# FrontPanel.net
KiCad netlist of a schematic drawn in EAGLE
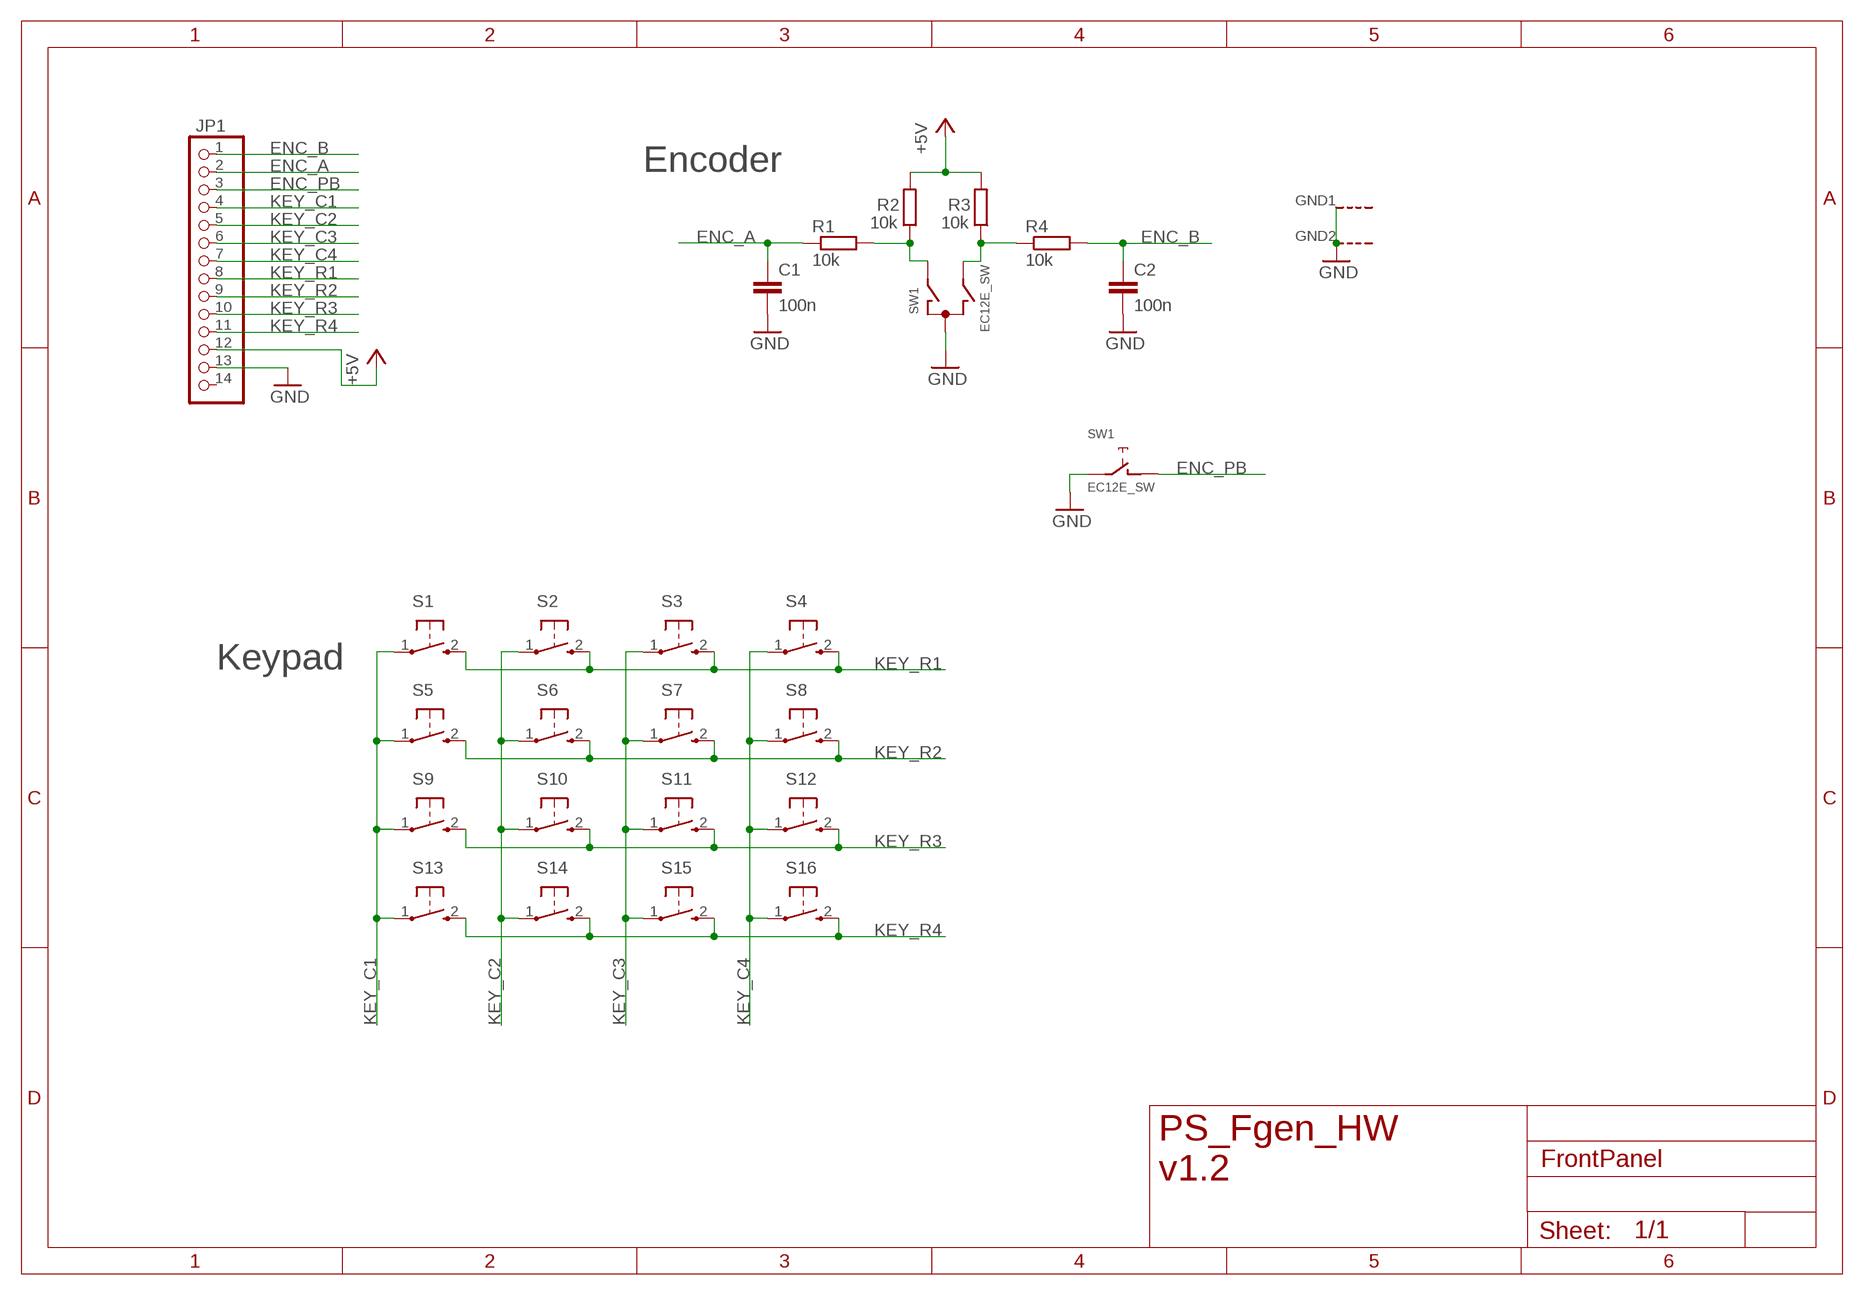
[diagram p0: schematic, sheet 1]

(export (version "E")
  (design (tool "Eeschema 10.0.6"))
  (components
    (comp (ref "C1")
      (value "100n")
      (footprint "eagle-import:C0805")
      (libsource (lib "eagle-import") (part "C-EUC0805"))
    )
    (comp (ref "C2")
      (value "100n")
      (footprint "eagle-import:C0805")
      (libsource (lib "eagle-import") (part "C-EUC0805"))
    )
    (comp (ref "JP1")
      (value "PINHD-1X14")
      (footprint "eagle-import:1X14")
      (libsource (lib "eagle-import") (part "PINHD-1X14"))
    )
    (comp (ref "R1")
      (value "10k")
      (footprint "eagle-import:R0805")
      (libsource (lib "eagle-import") (part "R-EU_R0805"))
    )
    (comp (ref "R2")
      (value "10k")
      (footprint "eagle-import:R0805")
      (libsource (lib "eagle-import") (part "R-EU_R0805"))
    )
    (comp (ref "R3")
      (value "10k")
      (footprint "eagle-import:R0805")
      (libsource (lib "eagle-import") (part "R-EU_R0805"))
    )
    (comp (ref "R4")
      (value "10k")
      (footprint "eagle-import:R0805")
      (libsource (lib "eagle-import") (part "R-EU_R0805"))
    )
    (comp (ref "S1")
      (value "KURZHUBTASTER")
      (footprint "eagle-import:B3F-10XX")
      (libsource (lib "eagle-import") (part "KURZHUBTASTER"))
    )
    (comp (ref "S2")
      (value "KURZHUBTASTER")
      (footprint "eagle-import:B3F-10XX")
      (libsource (lib "eagle-import") (part "KURZHUBTASTER"))
    )
    (comp (ref "S3")
      (value "KURZHUBTASTER")
      (footprint "eagle-import:B3F-10XX")
      (libsource (lib "eagle-import") (part "KURZHUBTASTER"))
    )
    (comp (ref "S4")
      (value "KURZHUBTASTER")
      (footprint "eagle-import:B3F-10XX")
      (libsource (lib "eagle-import") (part "KURZHUBTASTER"))
    )
    (comp (ref "S5")
      (value "KURZHUBTASTER")
      (footprint "eagle-import:B3F-10XX")
      (libsource (lib "eagle-import") (part "KURZHUBTASTER"))
    )
    (comp (ref "S6")
      (value "KURZHUBTASTER")
      (footprint "eagle-import:B3F-10XX")
      (libsource (lib "eagle-import") (part "KURZHUBTASTER"))
    )
    (comp (ref "S7")
      (value "KURZHUBTASTER")
      (footprint "eagle-import:B3F-10XX")
      (libsource (lib "eagle-import") (part "KURZHUBTASTER"))
    )
    (comp (ref "S8")
      (value "KURZHUBTASTER")
      (footprint "eagle-import:B3F-10XX")
      (libsource (lib "eagle-import") (part "KURZHUBTASTER"))
    )
    (comp (ref "S9")
      (value "KURZHUBTASTER")
      (footprint "eagle-import:B3F-10XX")
      (libsource (lib "eagle-import") (part "KURZHUBTASTER"))
    )
    (comp (ref "S10")
      (value "KURZHUBTASTER")
      (footprint "eagle-import:B3F-10XX")
      (libsource (lib "eagle-import") (part "KURZHUBTASTER"))
    )
    (comp (ref "S11")
      (value "KURZHUBTASTER")
      (footprint "eagle-import:B3F-10XX")
      (libsource (lib "eagle-import") (part "KURZHUBTASTER"))
    )
    (comp (ref "S12")
      (value "KURZHUBTASTER")
      (footprint "eagle-import:B3F-10XX")
      (libsource (lib "eagle-import") (part "KURZHUBTASTER"))
    )
    (comp (ref "S13")
      (value "KURZHUBTASTER")
      (footprint "eagle-import:B3F-10XX")
      (libsource (lib "eagle-import") (part "KURZHUBTASTER"))
    )
    (comp (ref "S14")
      (value "KURZHUBTASTER")
      (footprint "eagle-import:B3F-10XX")
      (libsource (lib "eagle-import") (part "KURZHUBTASTER"))
    )
    (comp (ref "S15")
      (value "KURZHUBTASTER")
      (footprint "eagle-import:B3F-10XX")
      (libsource (lib "eagle-import") (part "KURZHUBTASTER"))
    )
    (comp (ref "S16")
      (value "KURZHUBTASTER")
      (footprint "eagle-import:B3F-10XX")
      (libsource (lib "eagle-import") (part "KURZHUBTASTER"))
    )
    (comp (ref "SW1")
      (value "EC12E_SW")
      (footprint "eagle-import:ALPS_EC12E_SW")
      (fields (field (name "MPN") "EC12E2424407"))
      (libsource (lib "eagle-import") (part "EC12E_SW"))
    )
  )
  (nets
    (net (code "1") (name "+5V") (class "Default")
      (node (ref "JP1") (pin "12") (pinfunction "12_12") (pintype "passive"))
      (node (ref "R2") (pin "2") (pinfunction "2_2") (pintype "passive"))
      (node (ref "R3") (pin "2") (pinfunction "2_2") (pintype "passive"))
    )
    (net (code "2") (name "/ENC_A") (class "Default")
      (node (ref "C1") (pin "1") (pinfunction "1_1") (pintype "passive"))
      (node (ref "JP1") (pin "2") (pinfunction "2_2") (pintype "passive"))
      (node (ref "R1") (pin "1") (pinfunction "1_1") (pintype "passive"))
    )
    (net (code "3") (name "/ENC_B") (class "Default")
      (node (ref "C2") (pin "1") (pinfunction "1_1") (pintype "passive"))
      (node (ref "JP1") (pin "1") (pinfunction "1_1") (pintype "passive"))
      (node (ref "R4") (pin "2") (pinfunction "2_2") (pintype "passive"))
    )
    (net (code "4") (name "/ENC_PB") (class "Default")
      (node (ref "JP1") (pin "3") (pinfunction "3_3") (pintype "passive"))
      (node (ref "SW1") (pin "D") (pinfunction "1_D") (pintype "passive"))
    )
    (net (code "5") (name "/KEY_C1") (class "Default")
      (node (ref "JP1") (pin "4") (pinfunction "4_4") (pintype "passive"))
      (node (ref "S1") (pin "1") (pinfunction "P_1") (pintype "passive"))
      (node (ref "S13") (pin "1") (pinfunction "P_1") (pintype "passive"))
      (node (ref "S5") (pin "1") (pinfunction "P_1") (pintype "passive"))
      (node (ref "S9") (pin "1") (pinfunction "P_1") (pintype "passive"))
    )
    (net (code "6") (name "/KEY_C2") (class "Default")
      (node (ref "JP1") (pin "5") (pinfunction "5_5") (pintype "passive"))
      (node (ref "S10") (pin "1") (pinfunction "P_1") (pintype "passive"))
      (node (ref "S14") (pin "1") (pinfunction "P_1") (pintype "passive"))
      (node (ref "S2") (pin "1") (pinfunction "P_1") (pintype "passive"))
      (node (ref "S6") (pin "1") (pinfunction "P_1") (pintype "passive"))
    )
    (net (code "7") (name "/KEY_C3") (class "Default")
      (node (ref "JP1") (pin "6") (pinfunction "6_6") (pintype "passive"))
      (node (ref "S11") (pin "1") (pinfunction "P_1") (pintype "passive"))
      (node (ref "S15") (pin "1") (pinfunction "P_1") (pintype "passive"))
      (node (ref "S3") (pin "1") (pinfunction "P_1") (pintype "passive"))
      (node (ref "S7") (pin "1") (pinfunction "P_1") (pintype "passive"))
    )
    (net (code "8") (name "/KEY_C4") (class "Default")
      (node (ref "JP1") (pin "7") (pinfunction "7_7") (pintype "passive"))
      (node (ref "S12") (pin "1") (pinfunction "P_1") (pintype "passive"))
      (node (ref "S16") (pin "1") (pinfunction "P_1") (pintype "passive"))
      (node (ref "S4") (pin "1") (pinfunction "P_1") (pintype "passive"))
      (node (ref "S8") (pin "1") (pinfunction "P_1") (pintype "passive"))
    )
    (net (code "9") (name "/KEY_R1") (class "Default")
      (node (ref "JP1") (pin "8") (pinfunction "8_8") (pintype "passive"))
      (node (ref "S1") (pin "2") (pinfunction "S_2") (pintype "passive"))
      (node (ref "S2") (pin "2") (pinfunction "S_2") (pintype "passive"))
      (node (ref "S3") (pin "2") (pinfunction "S_2") (pintype "passive"))
      (node (ref "S4") (pin "2") (pinfunction "S_2") (pintype "passive"))
    )
    (net (code "10") (name "/KEY_R2") (class "Default")
      (node (ref "JP1") (pin "9") (pinfunction "9_9") (pintype "passive"))
      (node (ref "S5") (pin "2") (pinfunction "S_2") (pintype "passive"))
      (node (ref "S6") (pin "2") (pinfunction "S_2") (pintype "passive"))
      (node (ref "S7") (pin "2") (pinfunction "S_2") (pintype "passive"))
      (node (ref "S8") (pin "2") (pinfunction "S_2") (pintype "passive"))
    )
    (net (code "11") (name "/KEY_R3") (class "Default")
      (node (ref "JP1") (pin "10") (pinfunction "10_10") (pintype "passive"))
      (node (ref "S10") (pin "2") (pinfunction "S_2") (pintype "passive"))
      (node (ref "S11") (pin "2") (pinfunction "S_2") (pintype "passive"))
      (node (ref "S12") (pin "2") (pinfunction "S_2") (pintype "passive"))
      (node (ref "S9") (pin "2") (pinfunction "S_2") (pintype "passive"))
    )
    (net (code "12") (name "/KEY_R4") (class "Default")
      (node (ref "JP1") (pin "11") (pinfunction "11_11") (pintype "passive"))
      (node (ref "S13") (pin "2") (pinfunction "S_2") (pintype "passive"))
      (node (ref "S14") (pin "2") (pinfunction "S_2") (pintype "passive"))
      (node (ref "S15") (pin "2") (pinfunction "S_2") (pintype "passive"))
      (node (ref "S16") (pin "2") (pinfunction "S_2") (pintype "passive"))
    )
    (net (code "13") (name "GND") (class "Default")
      (node (ref "C1") (pin "2") (pinfunction "2_2") (pintype "passive"))
      (node (ref "C2") (pin "2") (pinfunction "2_2") (pintype "passive"))
      (node (ref "JP1") (pin "13") (pinfunction "13_13") (pintype "passive"))
      (node (ref "SW1") (pin "C") (pinfunction "C_C") (pintype "passive"))
      (node (ref "SW1") (pin "E") (pinfunction "2_E") (pintype "passive"))
      (node (ref "SW1") (pin "GND1") (pinfunction "G_GND1") (pintype "passive"))
      (node (ref "SW1") (pin "GND2") (pinfunction "G_GND2") (pintype "passive"))
    )
    (net (code "14") (name "Net-(R1-Pad2)") (class "Default")
      (node (ref "R1") (pin "2") (pinfunction "2_2") (pintype "passive"))
      (node (ref "R2") (pin "1") (pinfunction "1_1") (pintype "passive"))
      (node (ref "SW1") (pin "A") (pinfunction "A_A") (pintype "passive"))
    )
    (net (code "15") (name "Net-(R3-Pad1)") (class "Default")
      (node (ref "R3") (pin "1") (pinfunction "1_1") (pintype "passive"))
      (node (ref "R4") (pin "1") (pinfunction "1_1") (pintype "passive"))
      (node (ref "SW1") (pin "B") (pinfunction "B_B") (pintype "passive"))
    )
    (net (code "16") (name "unconnected-(JP1-Pad14)") (class "Default")
      (node (ref "JP1") (pin "14") (pinfunction "14_14") (pintype "passive"))
    )
  )
)
